# Sheet_1_2021-12-01.net
KiCad netlist of a schematic drawn in Altium Designer
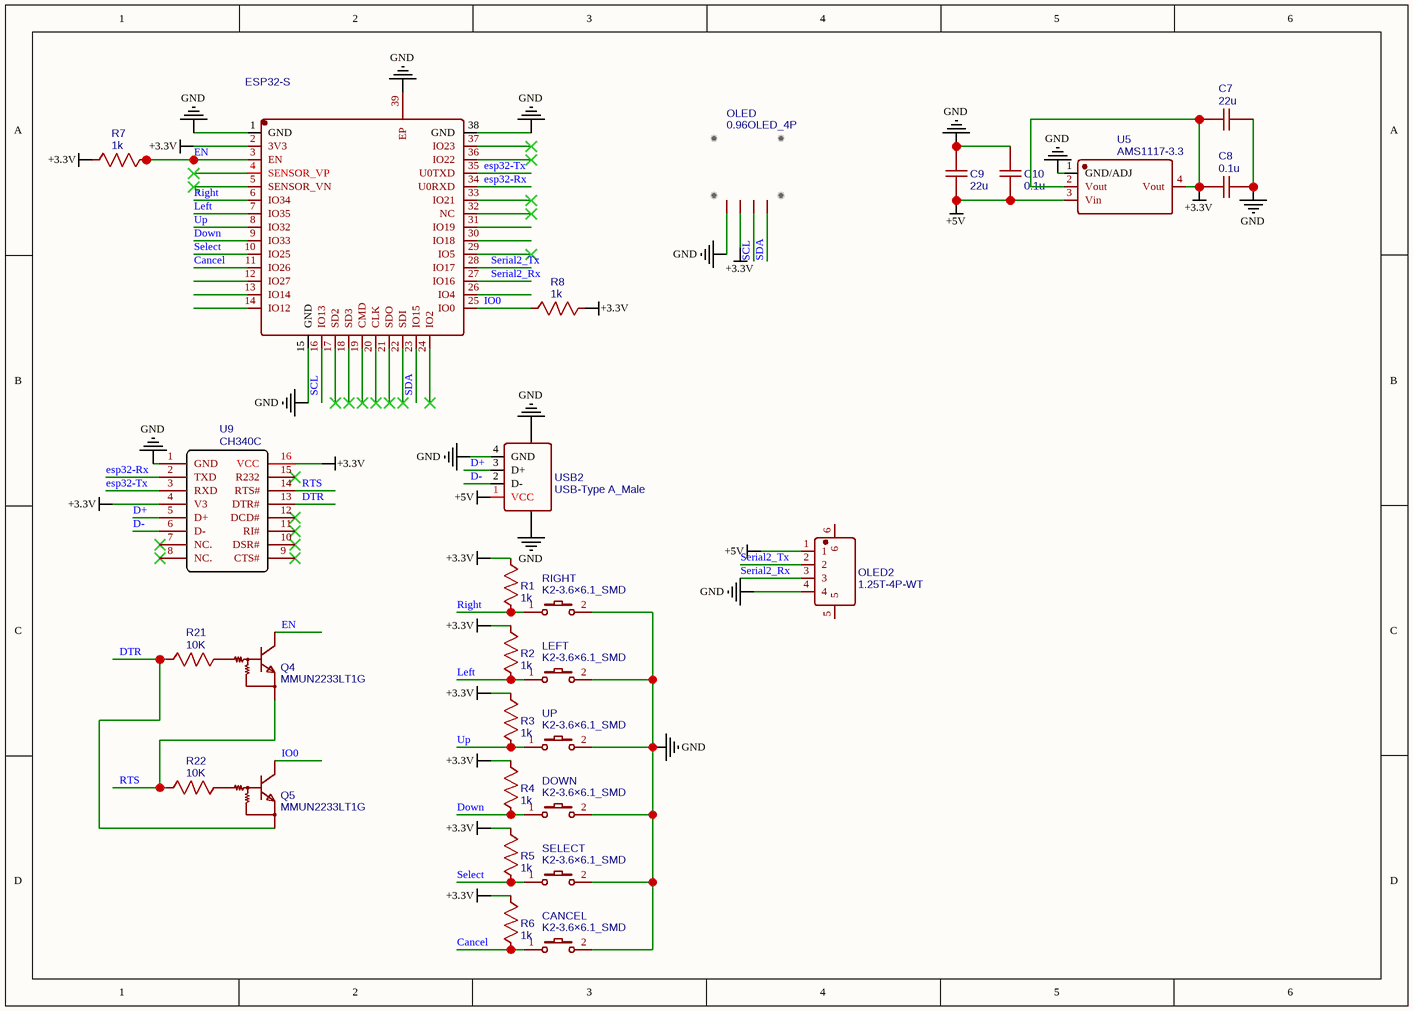
[diagram p0: Sheet_1_2021-12-01.schdoc]

(export (version "E")
  (design (tool "Eeschema 10.0.6"))
  (components
    (comp (ref "C7")
      (value "22u")
      (fields (field (name "CONTRIBUTOR") "LCEDA_Lib"))
      (libsource (lib "altium-import") (part "root_0_22u_"))
    )
    (comp (ref "C8")
      (value "0.1u")
      (fields (field (name "CONTRIBUTOR") "LCEDA_Lib"))
      (libsource (lib "altium-import") (part "root_0_0.1u_"))
    )
    (comp (ref "C9")
      (value "22u")
      (fields (field (name "CONTRIBUTOR") "LCEDA_Lib"))
      (libsource (lib "altium-import") (part "root_1_22u_"))
    )
    (comp (ref "C10")
      (value "0.1u")
      (fields (field (name "CONTRIBUTOR") "LCEDA_Lib"))
      (libsource (lib "altium-import") (part "root_1_0.1u_"))
    )
    (comp (ref "CANCEL")
      (value "K2-3.6×6.1_SMD")
      (fields
        (field (name "BOM_SUPPLIER PART") "C118141")
        (field (name "BOM_MANUFACTURER PART") "K2-1107ST-A4SW-06")
        (field (name "CONTRIBUTOR") "LCEDA_Lib")
      )
      (libsource (lib "altium-import") (part "root_0_K2-3.6×6.1_SMD_"))
    )
    (comp (ref "DOWN")
      (value "K2-3.6×6.1_SMD")
      (fields
        (field (name "BOM_SUPPLIER PART") "C118141")
        (field (name "BOM_MANUFACTURER PART") "K2-1107ST-A4SW-06")
        (field (name "CONTRIBUTOR") "LCEDA_Lib")
      )
      (libsource (lib "altium-import") (part "root_0_K2-3.6×6.1_SMD_"))
    )
    (comp (ref "ESP")
      (value "ESP32-S")
      (fields (field (name "BOM_SUPPLIER PART") "C277944") (field (name "CONTRIBUTOR") "LCSC"))
      (libsource (lib "altium-import") (part "root_0_ESP32-S_"))
    )
    (comp (ref "LEFT")
      (value "K2-3.6×6.1_SMD")
      (fields
        (field (name "BOM_SUPPLIER PART") "C118141")
        (field (name "BOM_MANUFACTURER PART") "K2-1107ST-A4SW-06")
        (field (name "CONTRIBUTOR") "LCEDA_Lib")
      )
      (libsource (lib "altium-import") (part "root_0_K2-3.6×6.1_SMD_"))
    )
    (comp (ref "OLED")
      (value "0.96OLED_4P")
      (fields (field (name "CONTRIBUTOR") "LCEDA_Lib"))
      (libsource (lib "altium-import") (part "root_0_0.96OLED_4P_"))
    )
    (comp (ref "OLED2")
      (value "1.25T-4P-WT")
      (fields (field (name "BOM_SUPPLIER PART") "C125739") (field (name "CONTRIBUTOR") "LCSC"))
      (libsource (lib "altium-import") (part "root_0_1.25T-4P-WT_"))
    )
    (comp (ref "Q4")
      (value "MMUN2233LT1G")
      (fields (field (name "BOM_SUPPLIER PART") "C86932"))
      (libsource (lib "altium-import") (part "root_0_MMUN2233LT1G_"))
    )
    (comp (ref "Q5")
      (value "MMUN2233LT1G")
      (fields (field (name "BOM_SUPPLIER PART") "C86932"))
      (libsource (lib "altium-import") (part "root_0_MMUN2233LT1G_"))
    )
    (comp (ref "R1")
      (value "1k")
      (fields (field (name "CONTRIBUTOR") "LCEDA_Lib"))
      (libsource (lib "altium-import") (part "root_1_1k_"))
    )
    (comp (ref "R2")
      (value "1k")
      (fields (field (name "CONTRIBUTOR") "LCEDA_Lib"))
      (libsource (lib "altium-import") (part "root_1_1k_"))
    )
    (comp (ref "R3")
      (value "1k")
      (fields (field (name "CONTRIBUTOR") "LCEDA_Lib"))
      (libsource (lib "altium-import") (part "root_1_1k_"))
    )
    (comp (ref "R4")
      (value "1k")
      (fields (field (name "CONTRIBUTOR") "LCEDA_Lib"))
      (libsource (lib "altium-import") (part "root_1_1k_"))
    )
    (comp (ref "R5")
      (value "1k")
      (fields (field (name "CONTRIBUTOR") "LCEDA_Lib"))
      (libsource (lib "altium-import") (part "root_1_1k_"))
    )
    (comp (ref "R6")
      (value "1k")
      (fields (field (name "CONTRIBUTOR") "LCEDA_Lib"))
      (libsource (lib "altium-import") (part "root_1_1k_"))
    )
    (comp (ref "R7")
      (value "1k")
      (fields (field (name "CONTRIBUTOR") "LCEDA_Lib"))
      (libsource (lib "altium-import") (part "root_2_1k_"))
    )
    (comp (ref "R8")
      (value "1k")
      (fields (field (name "CONTRIBUTOR") "LCEDA_Lib"))
      (libsource (lib "altium-import") (part "root_0_1k_"))
    )
    (comp (ref "R21")
      (value "10K")
      (fields (field (name "CONTRIBUTOR") "LCEDA_Lib"))
      (libsource (lib "altium-import") (part "root_0_10K_"))
    )
    (comp (ref "R22")
      (value "10K")
      (fields (field (name "CONTRIBUTOR") "LCEDA_Lib"))
      (libsource (lib "altium-import") (part "root_0_10K_"))
    )
    (comp (ref "RIGHT")
      (value "K2-3.6×6.1_SMD")
      (fields
        (field (name "BOM_SUPPLIER PART") "C118141")
        (field (name "BOM_MANUFACTURER PART") "K2-1107ST-A4SW-06")
        (field (name "CONTRIBUTOR") "LCEDA_Lib")
      )
      (libsource (lib "altium-import") (part "root_0_K2-3.6×6.1_SMD_"))
    )
    (comp (ref "SELECT")
      (value "K2-3.6×6.1_SMD")
      (fields
        (field (name "BOM_SUPPLIER PART") "C118141")
        (field (name "BOM_MANUFACTURER PART") "K2-1107ST-A4SW-06")
        (field (name "CONTRIBUTOR") "LCEDA_Lib")
      )
      (libsource (lib "altium-import") (part "root_0_K2-3.6×6.1_SMD_"))
    )
    (comp (ref "U5")
      (value "AMS1117-3.3")
      (fields (field (name "BOM_SUPPLIER PART") "C6186"))
      (libsource (lib "altium-import") (part "root_0_AMS1117-3.3_"))
    )
    (comp (ref "U9")
      (value "CH340C")
      (fields (field (name "BOM_SUPPLIER PART") "C84681"))
      (libsource (lib "altium-import") (part "root_0_CH340C_"))
    )
    (comp (ref "UP")
      (value "K2-3.6×6.1_SMD")
      (fields
        (field (name "BOM_SUPPLIER PART") "C118141")
        (field (name "BOM_MANUFACTURER PART") "K2-1107ST-A4SW-06")
        (field (name "CONTRIBUTOR") "LCEDA_Lib")
      )
      (libsource (lib "altium-import") (part "root_0_K2-3.6×6.1_SMD_"))
    )
    (comp (ref "USB2")
      (value "USB-Type A_Male")
      (fields
        (field (name "BOM_SUPPLIER PART") "C112454")
        (field (name "BOM_MANUFACTURER PART") "USB-05")
        (field (name "CONTRIBUTOR") "LCEDA_Lib")
      )
      (libsource (lib "altium-import") (part "root_2_USB-Type A_Male_"))
    )
  )
  (nets
    (net (code "1") (name "+3.3V") (class "Default")
      (node (ref "C7") (pin "1") (pinfunction "1_1") (pintype "passive"))
      (node (ref "C8") (pin "1") (pinfunction "1_1") (pintype "passive"))
      (node (ref "ESP") (pin "2") (pinfunction "3V3_2") (pintype "passive"))
      (node (ref "OLED") (pin "2") (pinfunction "2_2") (pintype "passive"))
      (node (ref "R1") (pin "2") (pinfunction "2_2") (pintype "passive"))
      (node (ref "R2") (pin "2") (pinfunction "2_2") (pintype "passive"))
      (node (ref "R3") (pin "2") (pinfunction "2_2") (pintype "passive"))
      (node (ref "R4") (pin "2") (pinfunction "2_2") (pintype "passive"))
      (node (ref "R5") (pin "2") (pinfunction "2_2") (pintype "passive"))
      (node (ref "R6") (pin "2") (pinfunction "2_2") (pintype "passive"))
      (node (ref "R7") (pin "2") (pinfunction "2_2") (pintype "passive"))
      (node (ref "R8") (pin "2") (pinfunction "2_2") (pintype "passive"))
      (node (ref "U5") (pin "2") (pinfunction "Vout_2") (pintype "passive"))
      (node (ref "U5") (pin "4") (pinfunction "Vout_4") (pintype "passive"))
      (node (ref "U9") (pin "16") (pinfunction "VCC_16") (pintype "passive"))
      (node (ref "U9") (pin "4") (pinfunction "V3_4") (pintype "passive"))
    )
    (net (code "2") (name "+5V") (class "Default")
      (node (ref "C10") (pin "1") (pinfunction "1_1") (pintype "passive"))
      (node (ref "C9") (pin "1") (pinfunction "1_1") (pintype "passive"))
      (node (ref "OLED2") (pin "1") (pinfunction "1_1") (pintype "passive"))
      (node (ref "U5") (pin "3") (pinfunction "Vin_3") (pintype "passive"))
      (node (ref "USB2") (pin "1") (pinfunction "VCC_1") (pintype "passive"))
    )
    (net (code "3") (name "/Cancel") (class "Default")
      (node (ref "CANCEL") (pin "1") (pinfunction "1_1") (pintype "passive"))
      (node (ref "ESP") (pin "11") (pinfunction "IO26_11") (pintype "passive"))
      (node (ref "R6") (pin "1") (pinfunction "1_1") (pintype "passive"))
    )
    (net (code "4") (name "/D+") (class "Default")
      (node (ref "U9") (pin "5") (pinfunction "D+_5") (pintype "passive"))
      (node (ref "USB2") (pin "3") (pinfunction "D+_3") (pintype "passive"))
    )
    (net (code "5") (name "/D-") (class "Default")
      (node (ref "U9") (pin "6") (pinfunction "D-_6") (pintype "passive"))
      (node (ref "USB2") (pin "2") (pinfunction "D-_2") (pintype "passive"))
    )
    (net (code "6") (name "/DTR") (class "Default")
      (node (ref "Q5") (pin "2") (pinfunction "E_2") (pintype "passive"))
      (node (ref "R21") (pin "1") (pinfunction "1_1") (pintype "passive"))
      (node (ref "U9") (pin "13") (pinfunction "DTR#_13") (pintype "passive"))
    )
    (net (code "7") (name "/Down") (class "Default")
      (node (ref "DOWN") (pin "1") (pinfunction "1_1") (pintype "passive"))
      (node (ref "ESP") (pin "9") (pinfunction "IO33_9") (pintype "passive"))
      (node (ref "R4") (pin "1") (pinfunction "1_1") (pintype "passive"))
    )
    (net (code "8") (name "/EN") (class "Default")
      (node (ref "ESP") (pin "3") (pinfunction "EN_3") (pintype "passive"))
      (node (ref "Q4") (pin "3") (pinfunction "C_3") (pintype "passive"))
      (node (ref "R7") (pin "1") (pinfunction "1_1") (pintype "passive"))
    )
    (net (code "9") (name "/IO0") (class "Default")
      (node (ref "ESP") (pin "25") (pinfunction "IO0_25") (pintype "passive"))
      (node (ref "Q5") (pin "3") (pinfunction "C_3") (pintype "passive"))
      (node (ref "R8") (pin "1") (pinfunction "1_1") (pintype "passive"))
    )
    (net (code "10") (name "/Left") (class "Default")
      (node (ref "ESP") (pin "7") (pinfunction "IO35_7") (pintype "passive"))
      (node (ref "LEFT") (pin "1") (pinfunction "1_1") (pintype "passive"))
      (node (ref "R2") (pin "1") (pinfunction "1_1") (pintype "passive"))
    )
    (net (code "11") (name "/RTS") (class "Default")
      (node (ref "Q4") (pin "2") (pinfunction "E_2") (pintype "passive"))
      (node (ref "R22") (pin "1") (pinfunction "1_1") (pintype "passive"))
      (node (ref "U9") (pin "14") (pinfunction "RTS#_14") (pintype "passive"))
    )
    (net (code "12") (name "/Right") (class "Default")
      (node (ref "ESP") (pin "6") (pinfunction "IO34_6") (pintype "passive"))
      (node (ref "R1") (pin "1") (pinfunction "1_1") (pintype "passive"))
      (node (ref "RIGHT") (pin "1") (pinfunction "1_1") (pintype "passive"))
    )
    (net (code "13") (name "/SCL") (class "Default")
      (node (ref "ESP") (pin "16") (pinfunction "IO13_16") (pintype "passive"))
      (node (ref "OLED") (pin "3") (pinfunction "3_3") (pintype "passive"))
    )
    (net (code "14") (name "/SDA") (class "Default")
      (node (ref "ESP") (pin "23") (pinfunction "IO15_23") (pintype "passive"))
      (node (ref "OLED") (pin "4") (pinfunction "4_4") (pintype "passive"))
    )
    (net (code "15") (name "/Select") (class "Default")
      (node (ref "ESP") (pin "10") (pinfunction "IO25_10") (pintype "passive"))
      (node (ref "R5") (pin "1") (pinfunction "1_1") (pintype "passive"))
      (node (ref "SELECT") (pin "1") (pinfunction "1_1") (pintype "passive"))
    )
    (net (code "16") (name "/Serial2_Rx") (class "Default")
      (node (ref "ESP") (pin "27") (pinfunction "IO16_27") (pintype "passive"))
      (node (ref "OLED2") (pin "3") (pinfunction "3_3") (pintype "passive"))
    )
    (net (code "17") (name "/Serial2_Tx") (class "Default")
      (node (ref "ESP") (pin "28") (pinfunction "IO17_28") (pintype "passive"))
      (node (ref "OLED2") (pin "2") (pinfunction "2_2") (pintype "passive"))
    )
    (net (code "18") (name "/Up") (class "Default")
      (node (ref "ESP") (pin "8") (pinfunction "IO32_8") (pintype "passive"))
      (node (ref "R3") (pin "1") (pinfunction "1_1") (pintype "passive"))
      (node (ref "UP") (pin "1") (pinfunction "1_1") (pintype "passive"))
    )
    (net (code "19") (name "/esp32-Rx") (class "Default")
      (node (ref "ESP") (pin "34") (pinfunction "U0RXD_34") (pintype "passive"))
      (node (ref "U9") (pin "2") (pinfunction "TXD_2") (pintype "passive"))
    )
    (net (code "20") (name "/esp32-Tx") (class "Default")
      (node (ref "ESP") (pin "35") (pinfunction "U0TXD_35") (pintype "passive"))
      (node (ref "U9") (pin "3") (pinfunction "RXD_3") (pintype "passive"))
    )
    (net (code "21") (name "GND") (class "Default")
      (node (ref "C10") (pin "2") (pinfunction "2_2") (pintype "passive"))
      (node (ref "C7") (pin "2") (pinfunction "2_2") (pintype "passive"))
      (node (ref "C8") (pin "2") (pinfunction "2_2") (pintype "passive"))
      (node (ref "C9") (pin "2") (pinfunction "2_2") (pintype "passive"))
      (node (ref "CANCEL") (pin "2") (pinfunction "2_2") (pintype "passive"))
      (node (ref "DOWN") (pin "2") (pinfunction "2_2") (pintype "passive"))
      (node (ref "ESP") (pin "1") (pinfunction "GND_1") (pintype "passive"))
      (node (ref "ESP") (pin "15") (pinfunction "GND_15") (pintype "passive"))
      (node (ref "ESP") (pin "38") (pinfunction "GND_38") (pintype "passive"))
      (node (ref "ESP") (pin "39") (pinfunction "EP_39") (pintype "passive"))
      (node (ref "LEFT") (pin "2") (pinfunction "2_2") (pintype "passive"))
      (node (ref "OLED") (pin "1") (pinfunction "1_1") (pintype "passive"))
      (node (ref "OLED2") (pin "4") (pinfunction "4_4") (pintype "passive"))
      (node (ref "RIGHT") (pin "2") (pinfunction "2_2") (pintype "passive"))
      (node (ref "SELECT") (pin "2") (pinfunction "2_2") (pintype "passive"))
      (node (ref "U5") (pin "1") (pinfunction "GND/ADJ_1") (pintype "passive"))
      (node (ref "U9") (pin "1") (pinfunction "GND_1") (pintype "passive"))
      (node (ref "UP") (pin "2") (pinfunction "2_2") (pintype "passive"))
      (node (ref "USB2") (pin "4") (pinfunction "GND_4") (pintype "passive"))
      (node (ref "USB2") (pin "5") (pinfunction "5_5") (pintype "passive"))
      (node (ref "USB2") (pin "6") (pinfunction "6_6") (pintype "passive"))
    )
    (net (code "22") (name "Net-(Q4-B)") (class "Default")
      (node (ref "Q4") (pin "1") (pinfunction "B_1") (pintype "passive"))
      (node (ref "R21") (pin "2") (pinfunction "2_2") (pintype "passive"))
    )
    (net (code "23") (name "Net-(Q5-B)") (class "Default")
      (node (ref "Q5") (pin "1") (pinfunction "B_1") (pintype "passive"))
      (node (ref "R22") (pin "2") (pinfunction "2_2") (pintype "passive"))
    )
    (net (code "24") (name "unconnected-(ESP-CLK-Pad20)") (class "Default")
      (node (ref "ESP") (pin "20") (pinfunction "CLK_20") (pintype "passive+no_connect"))
    )
    (net (code "25") (name "unconnected-(ESP-CMD-Pad19)") (class "Default")
      (node (ref "ESP") (pin "19") (pinfunction "CMD_19") (pintype "passive+no_connect"))
    )
    (net (code "26") (name "unconnected-(ESP-IO2-Pad24)") (class "Default")
      (node (ref "ESP") (pin "24") (pinfunction "IO2_24") (pintype "passive+no_connect"))
    )
    (net (code "27") (name "unconnected-(ESP-IO4-Pad26)") (class "Default")
      (node (ref "ESP") (pin "26") (pinfunction "IO4_26") (pintype "passive"))
    )
    (net (code "28") (name "unconnected-(ESP-IO5-Pad29)") (class "Default")
      (node (ref "ESP") (pin "29") (pinfunction "IO5_29") (pintype "passive+no_connect"))
    )
    (net (code "29") (name "unconnected-(ESP-IO12-Pad14)") (class "Default")
      (node (ref "ESP") (pin "14") (pinfunction "IO12_14") (pintype "passive"))
    )
    (net (code "30") (name "unconnected-(ESP-IO14-Pad13)") (class "Default")
      (node (ref "ESP") (pin "13") (pinfunction "IO14_13") (pintype "passive"))
    )
    (net (code "31") (name "unconnected-(ESP-IO18-Pad30)") (class "Default")
      (node (ref "ESP") (pin "30") (pinfunction "IO18_30") (pintype "passive"))
    )
    (net (code "32") (name "unconnected-(ESP-IO19-Pad31)") (class "Default")
      (node (ref "ESP") (pin "31") (pinfunction "IO19_31") (pintype "passive"))
    )
    (net (code "33") (name "unconnected-(ESP-IO21-Pad33)") (class "Default")
      (node (ref "ESP") (pin "33") (pinfunction "IO21_33") (pintype "passive+no_connect"))
    )
    (net (code "34") (name "unconnected-(ESP-IO22-Pad36)") (class "Default")
      (node (ref "ESP") (pin "36") (pinfunction "IO22_36") (pintype "passive+no_connect"))
    )
    (net (code "35") (name "unconnected-(ESP-IO23-Pad37)") (class "Default")
      (node (ref "ESP") (pin "37") (pinfunction "IO23_37") (pintype "passive+no_connect"))
    )
    (net (code "36") (name "unconnected-(ESP-IO27-Pad12)") (class "Default")
      (node (ref "ESP") (pin "12") (pinfunction "IO27_12") (pintype "passive"))
    )
    (net (code "37") (name "unconnected-(ESP-NC-Pad32)") (class "Default")
      (node (ref "ESP") (pin "32") (pinfunction "NC_32") (pintype "passive+no_connect"))
    )
    (net (code "38") (name "unconnected-(ESP-SD2-Pad17)") (class "Default")
      (node (ref "ESP") (pin "17") (pinfunction "SD2_17") (pintype "passive+no_connect"))
    )
    (net (code "39") (name "unconnected-(ESP-SD3-Pad18)") (class "Default")
      (node (ref "ESP") (pin "18") (pinfunction "SD3_18") (pintype "passive+no_connect"))
    )
    (net (code "40") (name "unconnected-(ESP-SDI-Pad22)") (class "Default")
      (node (ref "ESP") (pin "22") (pinfunction "SDI_22") (pintype "passive+no_connect"))
    )
    (net (code "41") (name "unconnected-(ESP-SDO-Pad21)") (class "Default")
      (node (ref "ESP") (pin "21") (pinfunction "SDO_21") (pintype "passive+no_connect"))
    )
    (net (code "42") (name "unconnected-(ESP-SENSOR_VN-Pad5)") (class "Default")
      (node (ref "ESP") (pin "5") (pinfunction "SENSOR_VN_5") (pintype "passive+no_connect"))
    )
    (net (code "43") (name "unconnected-(ESP-SENSOR_VP-Pad4)") (class "Default")
      (node (ref "ESP") (pin "4") (pinfunction "SENSOR_VP_4") (pintype "passive+no_connect"))
    )
    (net (code "44") (name "unconnected-(OLED2-Pad5)") (class "Default")
      (node (ref "OLED2") (pin "5") (pinfunction "5_5") (pintype "passive"))
    )
    (net (code "45") (name "unconnected-(OLED2-Pad6)") (class "Default")
      (node (ref "OLED2") (pin "6") (pinfunction "6_6") (pintype "passive"))
    )
    (net (code "46") (name "unconnected-(U9-CTS#-Pad9)") (class "Default")
      (node (ref "U9") (pin "9") (pinfunction "CTS#_9") (pintype "passive+no_connect"))
    )
    (net (code "47") (name "unconnected-(U9-DCD#-Pad12)") (class "Default")
      (node (ref "U9") (pin "12") (pinfunction "DCD#_12") (pintype "passive+no_connect"))
    )
    (net (code "48") (name "unconnected-(U9-DSR#-Pad10)") (class "Default")
      (node (ref "U9") (pin "10") (pinfunction "DSR#_10") (pintype "passive+no_connect"))
    )
    (net (code "49") (name "unconnected-(U9-NC.-Pad7)") (class "Default")
      (node (ref "U9") (pin "7") (pinfunction "NC._7") (pintype "passive+no_connect"))
    )
    (net (code "50") (name "unconnected-(U9-NC.-Pad8)") (class "Default")
      (node (ref "U9") (pin "8") (pinfunction "NC._8") (pintype "passive+no_connect"))
    )
    (net (code "51") (name "unconnected-(U9-R232-Pad15)") (class "Default")
      (node (ref "U9") (pin "15") (pinfunction "R232_15") (pintype "passive+no_connect"))
    )
    (net (code "52") (name "unconnected-(U9-RI#-Pad11)") (class "Default")
      (node (ref "U9") (pin "11") (pinfunction "RI#_11") (pintype "passive+no_connect"))
    )
  )
)
